# psychoholics_pin.net
KiCad netlist of a schematic drawn in EAGLE
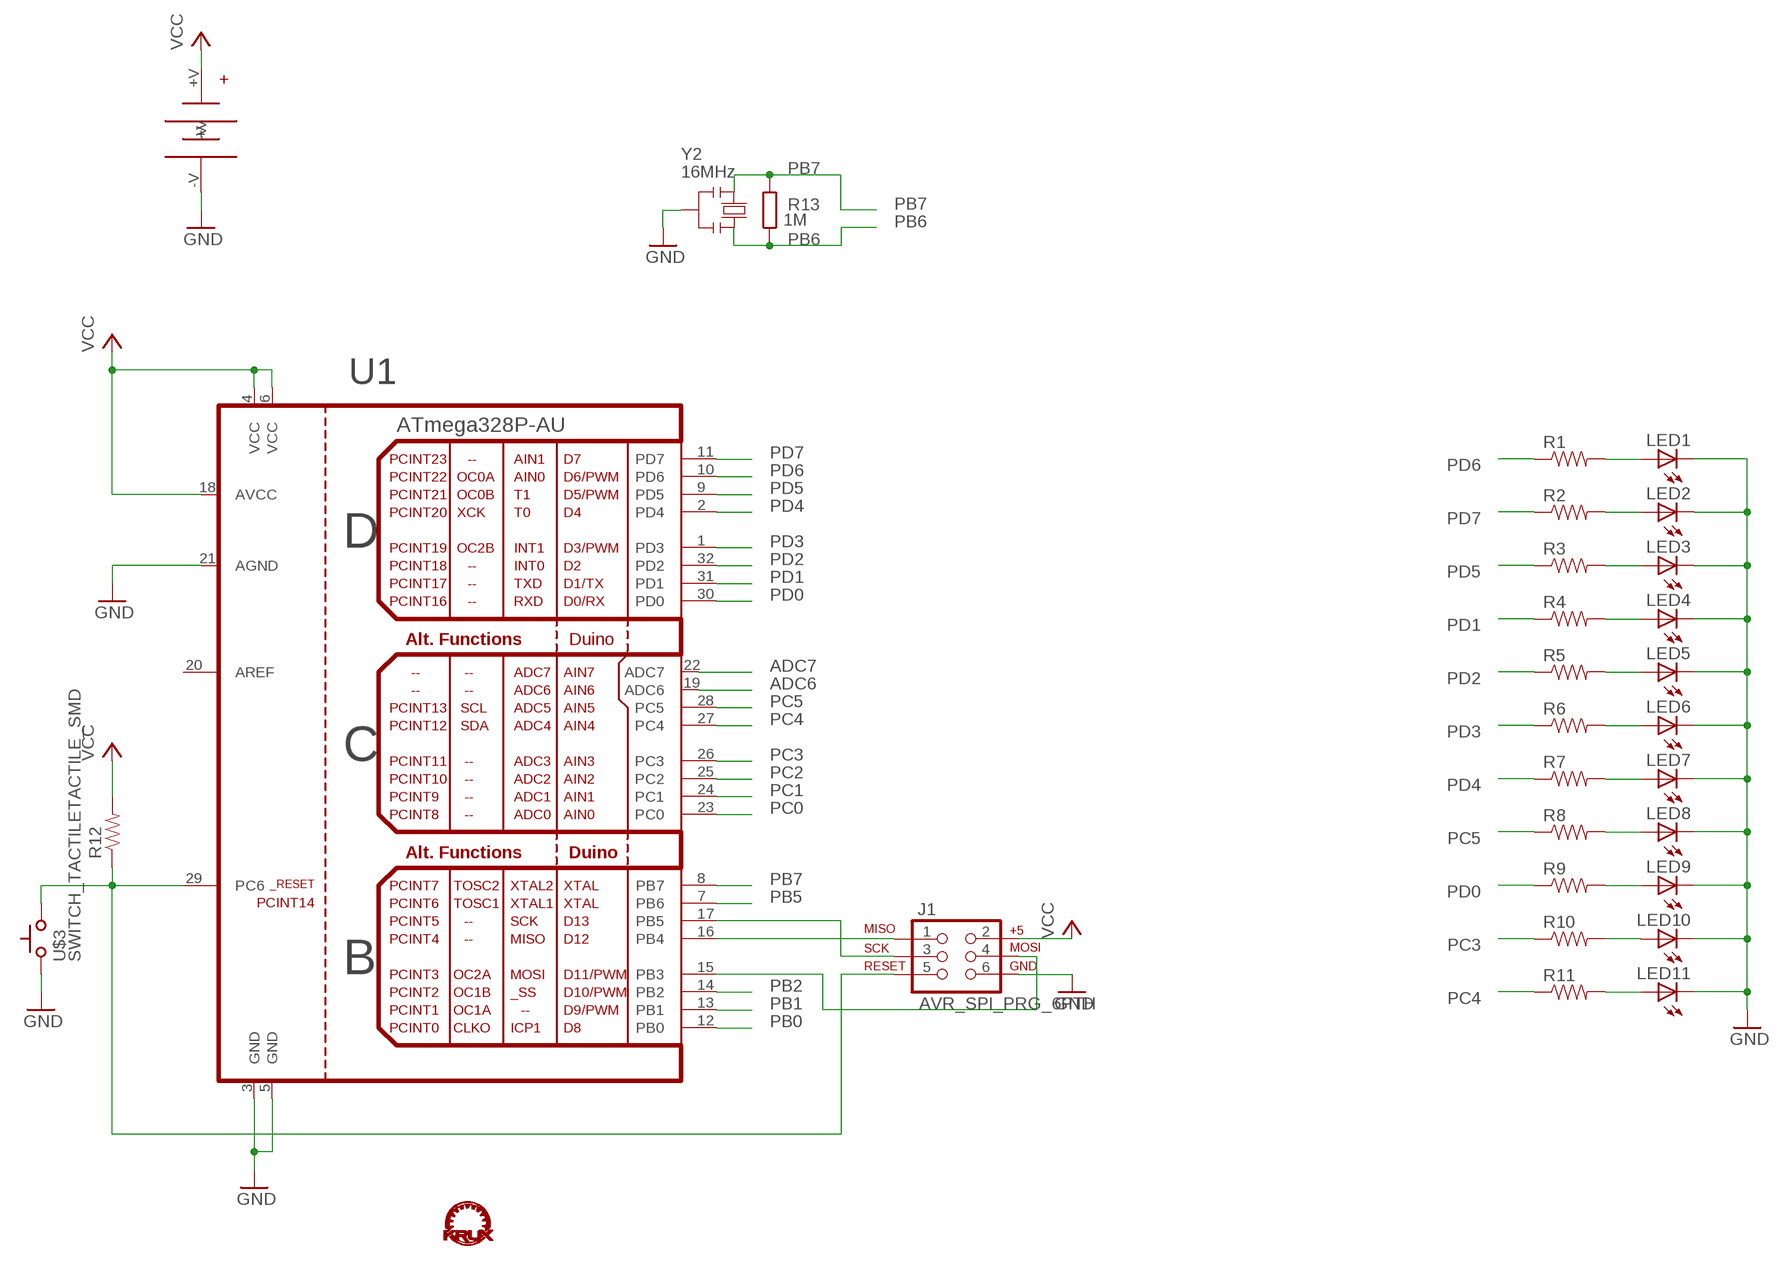
[diagram p0: schematic, sheet 1]

(export (version "E")
  (design (tool "Eeschema 10.0.6"))
  (components
    (comp (ref "J1")
      (value "AVR_SPI_PRG_6PTH")
      (footprint "eagle-import:2X3")
      (libsource (lib "eagle-import") (part "AVR_SPI_PRG_6PTH"))
    )
    (comp (ref "LED1")
      (value "LEDREVERSEMOUNT")
      (footprint "eagle-import:GULLWING_LED")
      (libsource (lib "eagle-import") (part "LEDREVERSEMOUNT"))
    )
    (comp (ref "LED2")
      (value "LEDREVERSEMOUNT")
      (footprint "eagle-import:GULLWING_LED")
      (libsource (lib "eagle-import") (part "LEDREVERSEMOUNT"))
    )
    (comp (ref "LED3")
      (value "LEDREVERSEMOUNT")
      (footprint "eagle-import:GULLWING_LED")
      (libsource (lib "eagle-import") (part "LEDREVERSEMOUNT"))
    )
    (comp (ref "LED4")
      (value "LEDREVERSEMOUNT")
      (footprint "eagle-import:GULLWING_LED")
      (libsource (lib "eagle-import") (part "LEDREVERSEMOUNT"))
    )
    (comp (ref "LED5")
      (value "LEDREVERSEMOUNT")
      (footprint "eagle-import:GULLWING_LED")
      (libsource (lib "eagle-import") (part "LEDREVERSEMOUNT"))
    )
    (comp (ref "LED6")
      (value "LEDREVERSEMOUNT")
      (footprint "eagle-import:GULLWING_LED")
      (libsource (lib "eagle-import") (part "LEDREVERSEMOUNT"))
    )
    (comp (ref "LED7")
      (value "LEDREVERSEMOUNT")
      (footprint "eagle-import:GULLWING_LED")
      (libsource (lib "eagle-import") (part "LEDREVERSEMOUNT"))
    )
    (comp (ref "LED8")
      (value "LEDREVERSEMOUNT")
      (footprint "eagle-import:GULLWING_LED")
      (libsource (lib "eagle-import") (part "LEDREVERSEMOUNT"))
    )
    (comp (ref "LED9")
      (value "LEDREVERSEMOUNT")
      (footprint "eagle-import:GULLWING_LED")
      (libsource (lib "eagle-import") (part "LEDREVERSEMOUNT"))
    )
    (comp (ref "LED10")
      (value "LEDREVERSEMOUNT")
      (footprint "eagle-import:GULLWING_LED")
      (libsource (lib "eagle-import") (part "LEDREVERSEMOUNT"))
    )
    (comp (ref "LED11")
      (value "LEDREVERSEMOUNT")
      (footprint "eagle-import:GULLWING_LED")
      (libsource (lib "eagle-import") (part "LEDREVERSEMOUNT"))
    )
    (comp (ref "R1")
      (value "RESISTOR0603-RES")
      (footprint "eagle-import:0603-RES")
      (libsource (lib "eagle-import") (part "RESISTOR0603-RES"))
    )
    (comp (ref "R2")
      (value "RESISTOR0603-RES")
      (footprint "eagle-import:0603-RES")
      (libsource (lib "eagle-import") (part "RESISTOR0603-RES"))
    )
    (comp (ref "R3")
      (value "RESISTOR0603-RES")
      (footprint "eagle-import:0603-RES")
      (libsource (lib "eagle-import") (part "RESISTOR0603-RES"))
    )
    (comp (ref "R4")
      (value "RESISTOR0603-RES")
      (footprint "eagle-import:0603-RES")
      (libsource (lib "eagle-import") (part "RESISTOR0603-RES"))
    )
    (comp (ref "R5")
      (value "RESISTOR0603-RES")
      (footprint "eagle-import:0603-RES")
      (libsource (lib "eagle-import") (part "RESISTOR0603-RES"))
    )
    (comp (ref "R6")
      (value "RESISTOR0603-RES")
      (footprint "eagle-import:0603-RES")
      (libsource (lib "eagle-import") (part "RESISTOR0603-RES"))
    )
    (comp (ref "R7")
      (value "RESISTOR0603-RES")
      (footprint "eagle-import:0603-RES")
      (libsource (lib "eagle-import") (part "RESISTOR0603-RES"))
    )
    (comp (ref "R8")
      (value "RESISTOR0603-RES")
      (footprint "eagle-import:0603-RES")
      (libsource (lib "eagle-import") (part "RESISTOR0603-RES"))
    )
    (comp (ref "R9")
      (value "RESISTOR0603-RES")
      (footprint "eagle-import:0603-RES")
      (libsource (lib "eagle-import") (part "RESISTOR0603-RES"))
    )
    (comp (ref "R10")
      (value "RESISTOR0603-RES")
      (footprint "eagle-import:0603-RES")
      (libsource (lib "eagle-import") (part "RESISTOR0603-RES"))
    )
    (comp (ref "R11")
      (value "RESISTOR0603-RES")
      (footprint "eagle-import:0603-RES")
      (libsource (lib "eagle-import") (part "RESISTOR0603-RES"))
    )
    (comp (ref "R12")
      (value "RESISTOR0603-RES")
      (footprint "eagle-import:0603-RES")
      (libsource (lib "eagle-import") (part "RESISTOR0603-RES"))
    )
    (comp (ref "R13")
      (value "1M")
      (footprint "eagle-import:R0603-ROUND")
      (libsource (lib "eagle-import") (part "R-EU_R0603"))
    )
    (comp (ref "U$1")
      (value "KRUX_LOGO")
      (footprint "eagle-import:KRUX_LOGO")
      (libsource (lib "eagle-import") (part "KRUX_LOGO"))
    )
    (comp (ref "U$2")
      (value "12BH423-GR12BH423-GR_NOBORDER")
      (footprint "eagle-import:12BH423-GR_NOBORDER")
      (libsource (lib "eagle-import") (part "12BH423-GR12BH423-GR_NOBORDER"))
    )
    (comp (ref "U$3")
      (value "SWITCH_TACTILETACTILE_SMD")
      (footprint "eagle-import:TACTILE_SWITCH_SMD")
      (libsource (lib "eagle-import") (part "SWITCH_TACTILETACTILE_SMD"))
    )
    (comp (ref "U1")
      (value "ATmega328P-AU")
      (footprint "eagle-import:TQFP-32-08-THIN")
      (libsource (lib "eagle-import") (part "ATMEGA328TQFP-32-08-THIN"))
    )
    (comp (ref "Y2")
      (value "16MHz")
      (footprint "eagle-import:RESONATOR")
      (libsource (lib "eagle-import") (part "RESONATORMU"))
    )
  )
  (nets
    (net (code "1") (name "/ADC6") (class "Default")
      (node (ref "U1") (pin "19") (pinfunction "ADC6_19") (pintype "bidirectional"))
    )
    (net (code "2") (name "/ADC7") (class "Default")
      (node (ref "U1") (pin "22") (pinfunction "ADC7_22") (pintype "bidirectional"))
    )
    (net (code "3") (name "/PB0") (class "Default")
      (node (ref "U1") (pin "12") (pinfunction "PB0_12") (pintype "bidirectional"))
    )
    (net (code "4") (name "/PB1") (class "Default")
      (node (ref "U1") (pin "13") (pinfunction "PB1_13") (pintype "bidirectional"))
    )
    (net (code "5") (name "/PB2") (class "Default")
      (node (ref "U1") (pin "14") (pinfunction "PB2_14") (pintype "bidirectional"))
    )
    (net (code "6") (name "/PB5") (class "Default")
      (node (ref "J1") (pin "3") (pinfunction "3_3") (pintype "passive"))
      (node (ref "U1") (pin "17") (pinfunction "PB5_17") (pintype "bidirectional"))
    )
    (net (code "7") (name "/PB6") (class "Default")
      (node (ref "R13") (pin "1") (pinfunction "1_1") (pintype "passive"))
      (node (ref "U1") (pin "7") (pinfunction "PB6_7") (pintype "bidirectional"))
      (node (ref "Y2") (pin "3") (pinfunction "3_3") (pintype "passive"))
    )
    (net (code "8") (name "/PB7") (class "Default")
      (node (ref "R13") (pin "2") (pinfunction "2_2") (pintype "passive"))
      (node (ref "U1") (pin "8") (pinfunction "PB7_8") (pintype "bidirectional"))
      (node (ref "Y2") (pin "1") (pinfunction "1_1") (pintype "passive"))
    )
    (net (code "9") (name "/PC0") (class "Default")
      (node (ref "U1") (pin "23") (pinfunction "PC0_23") (pintype "bidirectional"))
    )
    (net (code "10") (name "/PC1") (class "Default")
      (node (ref "U1") (pin "24") (pinfunction "PC1_24") (pintype "bidirectional"))
    )
    (net (code "11") (name "/PC2") (class "Default")
      (node (ref "U1") (pin "25") (pinfunction "PC2_25") (pintype "bidirectional"))
    )
    (net (code "12") (name "/PC3") (class "Default")
      (node (ref "R10") (pin "1") (pinfunction "1_1") (pintype "passive"))
      (node (ref "U1") (pin "26") (pinfunction "PC3_26") (pintype "bidirectional"))
    )
    (net (code "13") (name "/PC4") (class "Default")
      (node (ref "R11") (pin "1") (pinfunction "1_1") (pintype "passive"))
      (node (ref "U1") (pin "27") (pinfunction "PC4_27") (pintype "bidirectional"))
    )
    (net (code "14") (name "/PC5") (class "Default")
      (node (ref "R8") (pin "1") (pinfunction "1_1") (pintype "passive"))
      (node (ref "U1") (pin "28") (pinfunction "PC5_28") (pintype "bidirectional"))
    )
    (net (code "15") (name "/PD0") (class "Default")
      (node (ref "R9") (pin "1") (pinfunction "1_1") (pintype "passive"))
      (node (ref "U1") (pin "30") (pinfunction "PD0_30") (pintype "bidirectional"))
    )
    (net (code "16") (name "/PD1") (class "Default")
      (node (ref "R4") (pin "1") (pinfunction "1_1") (pintype "passive"))
      (node (ref "U1") (pin "31") (pinfunction "PD1_31") (pintype "bidirectional"))
    )
    (net (code "17") (name "/PD2") (class "Default")
      (node (ref "R5") (pin "1") (pinfunction "1_1") (pintype "passive"))
      (node (ref "U1") (pin "32") (pinfunction "PD2_32") (pintype "bidirectional"))
    )
    (net (code "18") (name "/PD3") (class "Default")
      (node (ref "R6") (pin "1") (pinfunction "1_1") (pintype "passive"))
      (node (ref "U1") (pin "1") (pinfunction "PD3_1") (pintype "bidirectional"))
    )
    (net (code "19") (name "/PD4") (class "Default")
      (node (ref "R7") (pin "1") (pinfunction "1_1") (pintype "passive"))
      (node (ref "U1") (pin "2") (pinfunction "PD4_2") (pintype "bidirectional"))
    )
    (net (code "20") (name "/PD5") (class "Default")
      (node (ref "R3") (pin "1") (pinfunction "1_1") (pintype "passive"))
      (node (ref "U1") (pin "9") (pinfunction "PD5_9") (pintype "bidirectional"))
    )
    (net (code "21") (name "/PD6") (class "Default")
      (node (ref "R1") (pin "1") (pinfunction "1_1") (pintype "passive"))
      (node (ref "U1") (pin "10") (pinfunction "PD6_10") (pintype "bidirectional"))
    )
    (net (code "22") (name "/PD7") (class "Default")
      (node (ref "R2") (pin "1") (pinfunction "1_1") (pintype "passive"))
      (node (ref "U1") (pin "11") (pinfunction "PD7_11") (pintype "bidirectional"))
    )
    (net (code "23") (name "GND") (class "Default")
      (node (ref "J1") (pin "6") (pinfunction "6_6") (pintype "passive"))
      (node (ref "LED1") (pin "C") (pinfunction "C_C") (pintype "output"))
      (node (ref "LED10") (pin "C") (pinfunction "C_C") (pintype "output"))
      (node (ref "LED11") (pin "C") (pinfunction "C_C") (pintype "output"))
      (node (ref "LED2") (pin "C") (pinfunction "C_C") (pintype "output"))
      (node (ref "LED3") (pin "C") (pinfunction "C_C") (pintype "output"))
      (node (ref "LED4") (pin "C") (pinfunction "C_C") (pintype "output"))
      (node (ref "LED5") (pin "C") (pinfunction "C_C") (pintype "output"))
      (node (ref "LED6") (pin "C") (pinfunction "C_C") (pintype "output"))
      (node (ref "LED7") (pin "C") (pinfunction "C_C") (pintype "output"))
      (node (ref "LED8") (pin "C") (pinfunction "C_C") (pintype "output"))
      (node (ref "LED9") (pin "C") (pinfunction "C_C") (pintype "output"))
      (node (ref "U$2") (pin "-V") (pinfunction "-V_-V") (pintype "bidirectional"))
      (node (ref "U$3") (pin "3") (pinfunction "C_3") (pintype "passive"))
      (node (ref "U$3") (pin "4") (pinfunction "C_4") (pintype "passive"))
      (node (ref "U1") (pin "21") (pinfunction "AGND_21") (pintype "power_in"))
      (node (ref "U1") (pin "3") (pinfunction "GND_3") (pintype "power_in"))
      (node (ref "U1") (pin "5") (pinfunction "GND_5") (pintype "power_in"))
      (node (ref "Y2") (pin "2") (pinfunction "2_2") (pintype "passive"))
    )
    (net (code "24") (name "Net-(LED1-PadA)") (class "Default")
      (node (ref "LED1") (pin "A") (pinfunction "A_A") (pintype "input"))
      (node (ref "R1") (pin "2") (pinfunction "2_2") (pintype "passive"))
    )
    (net (code "25") (name "Net-(LED2-PadA)") (class "Default")
      (node (ref "LED2") (pin "A") (pinfunction "A_A") (pintype "input"))
      (node (ref "R2") (pin "2") (pinfunction "2_2") (pintype "passive"))
    )
    (net (code "26") (name "Net-(LED3-PadA)") (class "Default")
      (node (ref "LED3") (pin "A") (pinfunction "A_A") (pintype "input"))
      (node (ref "R3") (pin "2") (pinfunction "2_2") (pintype "passive"))
    )
    (net (code "27") (name "Net-(LED4-PadA)") (class "Default")
      (node (ref "LED4") (pin "A") (pinfunction "A_A") (pintype "input"))
      (node (ref "R4") (pin "2") (pinfunction "2_2") (pintype "passive"))
    )
    (net (code "28") (name "Net-(LED5-PadA)") (class "Default")
      (node (ref "LED5") (pin "A") (pinfunction "A_A") (pintype "input"))
      (node (ref "R5") (pin "2") (pinfunction "2_2") (pintype "passive"))
    )
    (net (code "29") (name "Net-(LED6-PadA)") (class "Default")
      (node (ref "LED6") (pin "A") (pinfunction "A_A") (pintype "input"))
      (node (ref "R6") (pin "2") (pinfunction "2_2") (pintype "passive"))
    )
    (net (code "30") (name "Net-(LED7-PadA)") (class "Default")
      (node (ref "LED7") (pin "A") (pinfunction "A_A") (pintype "input"))
      (node (ref "R7") (pin "2") (pinfunction "2_2") (pintype "passive"))
    )
    (net (code "31") (name "Net-(LED8-PadA)") (class "Default")
      (node (ref "LED8") (pin "A") (pinfunction "A_A") (pintype "input"))
      (node (ref "R8") (pin "2") (pinfunction "2_2") (pintype "passive"))
    )
    (net (code "32") (name "Net-(LED9-PadA)") (class "Default")
      (node (ref "LED9") (pin "A") (pinfunction "A_A") (pintype "input"))
      (node (ref "R9") (pin "2") (pinfunction "2_2") (pintype "passive"))
    )
    (net (code "33") (name "Net-(LED10-PadA)") (class "Default")
      (node (ref "LED10") (pin "A") (pinfunction "A_A") (pintype "input"))
      (node (ref "R10") (pin "2") (pinfunction "2_2") (pintype "passive"))
    )
    (net (code "34") (name "Net-(LED11-PadA)") (class "Default")
      (node (ref "LED11") (pin "A") (pinfunction "A_A") (pintype "input"))
      (node (ref "R11") (pin "2") (pinfunction "2_2") (pintype "passive"))
    )
    (net (code "35") (name "Net-(U1-PB3)") (class "Default")
      (node (ref "J1") (pin "4") (pinfunction "4_4") (pintype "passive"))
      (node (ref "U1") (pin "15") (pinfunction "PB3_15") (pintype "bidirectional"))
    )
    (net (code "36") (name "Net-(U1-PB4)") (class "Default")
      (node (ref "J1") (pin "1") (pinfunction "1_1") (pintype "passive"))
      (node (ref "U1") (pin "16") (pinfunction "PB4_16") (pintype "bidirectional"))
    )
    (net (code "37") (name "Net-(U1-PC6)") (class "Default")
      (node (ref "J1") (pin "5") (pinfunction "5_5") (pintype "passive"))
      (node (ref "R12") (pin "1") (pinfunction "1_1") (pintype "passive"))
      (node (ref "U$3") (pin "1") (pinfunction "A_1") (pintype "passive"))
      (node (ref "U$3") (pin "2") (pinfunction "A_2") (pintype "passive"))
      (node (ref "U1") (pin "29") (pinfunction "PC6_29") (pintype "bidirectional"))
    )
    (net (code "38") (name "VCC") (class "Default")
      (node (ref "J1") (pin "2") (pinfunction "2_2") (pintype "passive"))
      (node (ref "R12") (pin "2") (pinfunction "2_2") (pintype "passive"))
      (node (ref "U$2") (pin "+V") (pinfunction "+V_+V") (pintype "bidirectional"))
      (node (ref "U1") (pin "18") (pinfunction "AVCC_18") (pintype "power_in"))
      (node (ref "U1") (pin "4") (pinfunction "VCC_4") (pintype "power_in"))
      (node (ref "U1") (pin "6") (pinfunction "VCC_6") (pintype "power_in"))
    )
    (net (code "39") (name "unconnected-(U1-AREF-Pad20)") (class "Default")
      (node (ref "U1") (pin "20") (pinfunction "AREF_20") (pintype "input"))
    )
  )
)
